# RGB_Station_v12.net
KiCad netlist of a schematic drawn in EAGLE
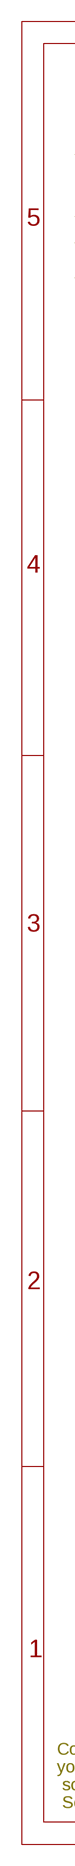
[diagram p0: schematic, sheet 1, part 1 of 2]
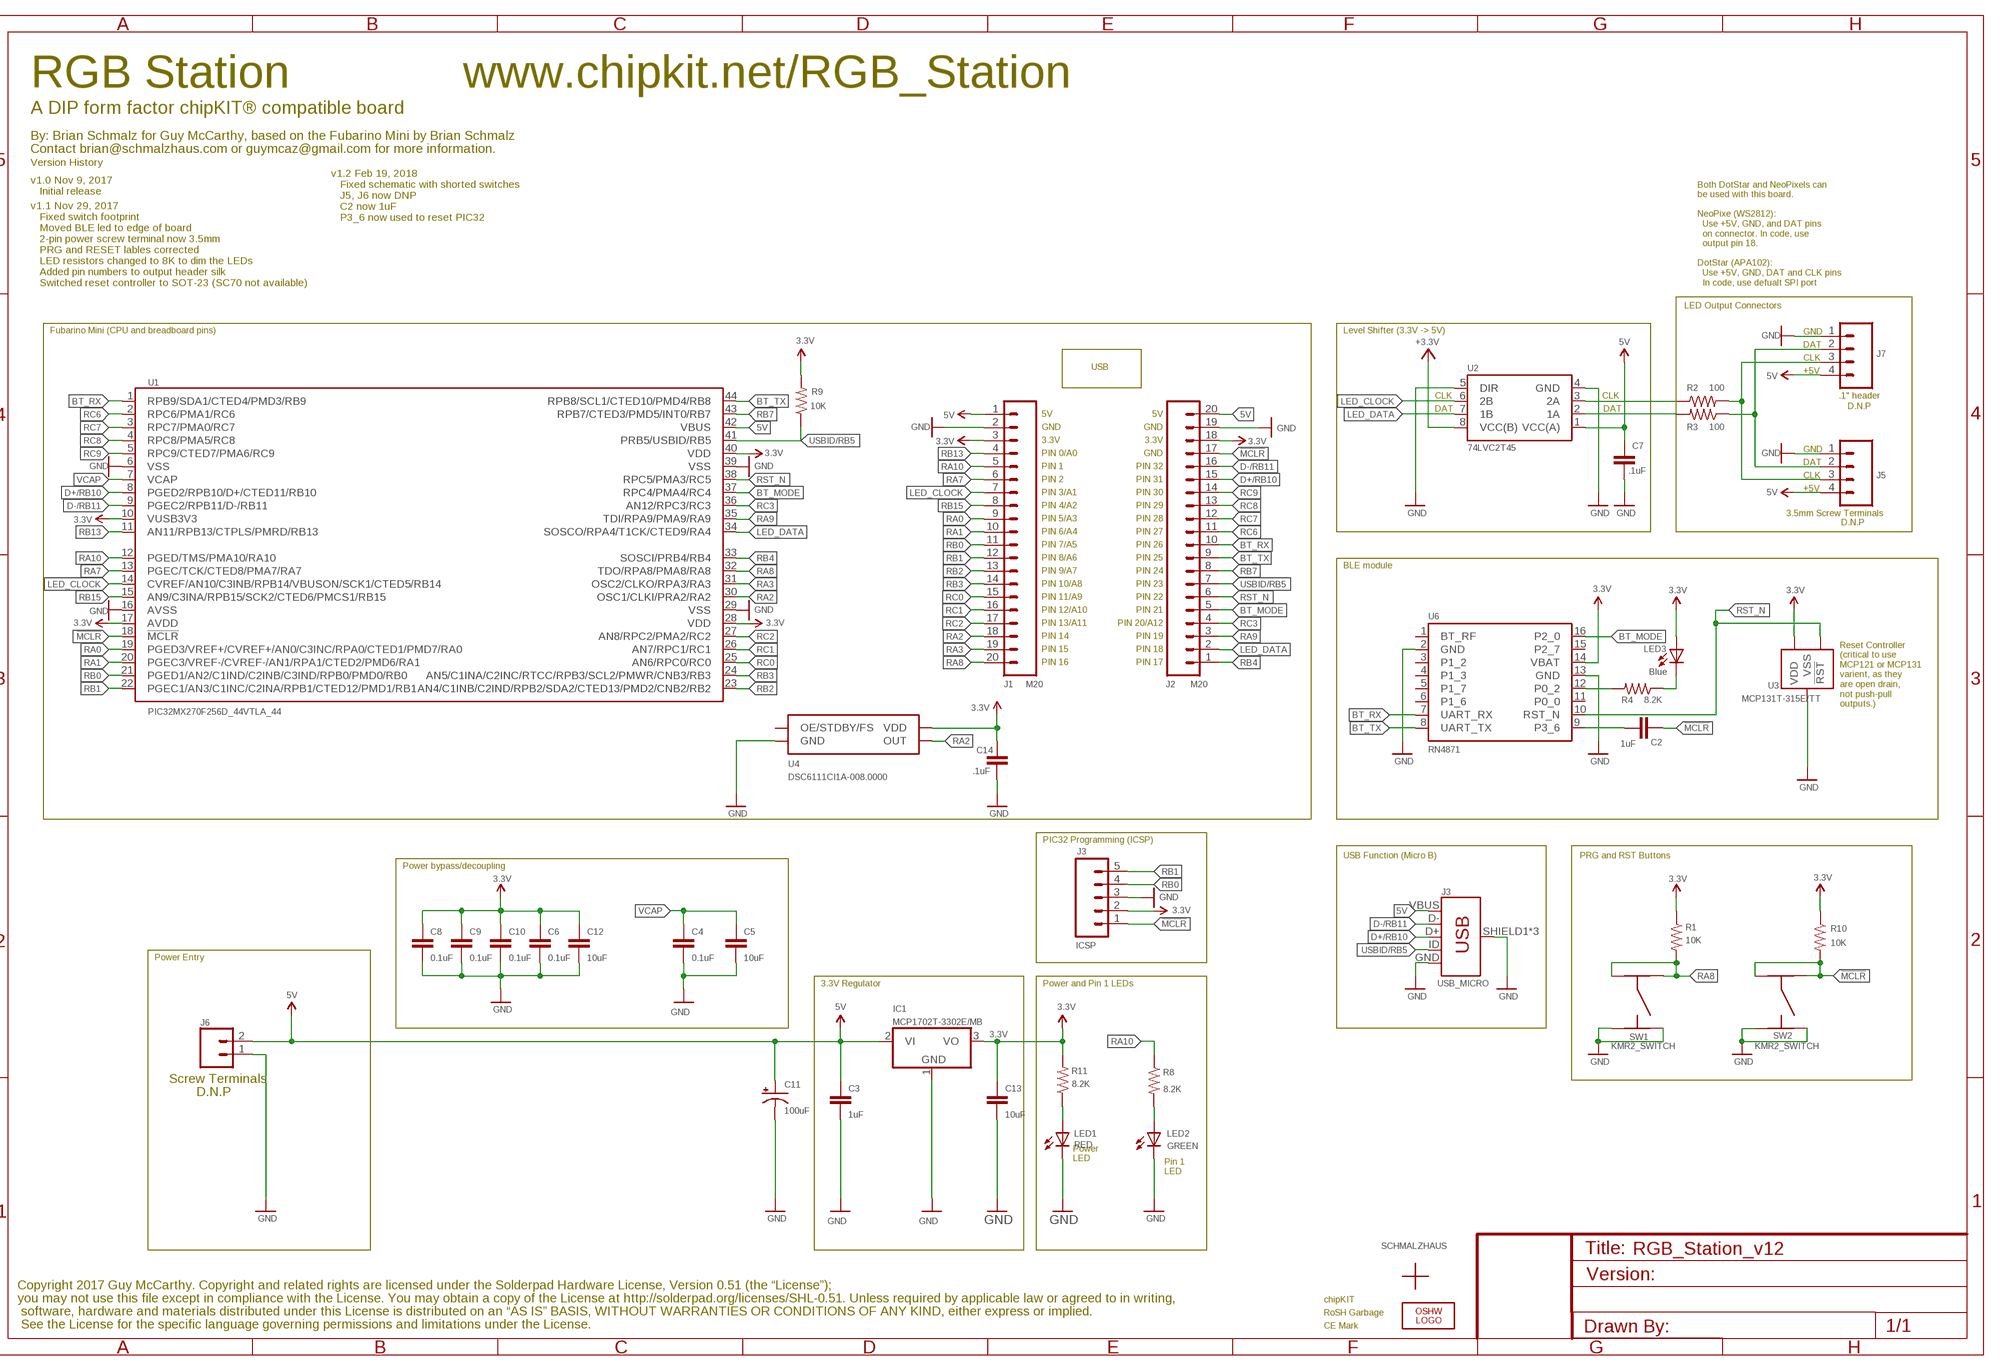
[diagram p1: schematic, sheet 1, part 2 of 2]

(export (version "E")
  (design (tool "Eeschema 10.0.6"))
  (components
    (comp (ref "C2")
      (value "1uF")
      (footprint "eagle-import:0603-CAP")
      (libsource (lib "eagle-import") (part "SparkFun-Capacitors_CAP0603-CAP"))
    )
    (comp (ref "C3")
      (value "1uF")
      (footprint "eagle-import:0603-CAP")
      (libsource (lib "eagle-import") (part "SparkFun_CAP0603-CAP"))
    )
    (comp (ref "C4")
      (value "0.1uF")
      (footprint "eagle-import:0603-CAP")
      (libsource (lib "eagle-import") (part "SparkFun_CAP0603-CAP"))
    )
    (comp (ref "C5")
      (value "10uF")
      (footprint "eagle-import:0805")
      (libsource (lib "eagle-import") (part "CAP0805"))
    )
    (comp (ref "C6")
      (value "0.1uF")
      (footprint "eagle-import:0603")
      (libsource (lib "eagle-import") (part "CAP0603"))
    )
    (comp (ref "C7")
      (value ".1uF")
      (footprint "eagle-import:0603-CAP")
      (libsource (lib "eagle-import") (part "SparkFun-Capacitors_CAP0603-CAP"))
    )
    (comp (ref "C8")
      (value "0.1uF")
      (footprint "eagle-import:0603-CAP")
      (libsource (lib "eagle-import") (part "SparkFun_CAP0603-CAP"))
    )
    (comp (ref "C9")
      (value "0.1uF")
      (footprint "eagle-import:0603-CAP")
      (libsource (lib "eagle-import") (part "SparkFun_CAP0603-CAP"))
    )
    (comp (ref "C10")
      (value "0.1uF")
      (footprint "eagle-import:0603")
      (libsource (lib "eagle-import") (part "CAP0603"))
    )
    (comp (ref "C11")
      (value "100uF")
      (footprint "eagle-import:PANASONIC_C")
      (libsource (lib "eagle-import") (part "CAP_POLC"))
    )
    (comp (ref "C12")
      (value "10uF")
      (footprint "eagle-import:0805")
      (libsource (lib "eagle-import") (part "CAP0805"))
    )
    (comp (ref "C13")
      (value "10uF")
      (footprint "eagle-import:0805")
      (libsource (lib "eagle-import") (part "SparkFun02-20-08_CAP0805"))
    )
    (comp (ref "C14")
      (value ".1uF")
      (footprint "eagle-import:0603-CAP")
      (libsource (lib "eagle-import") (part "SparkFun_CAP0603-CAP"))
    )
    (comp (ref "IC1")
      (value "MCP1702T-3302E/MB")
      (footprint "eagle-import:RGB_STATION_V12_LINEAR_SOT89")
      (libsource (lib "eagle-import") (part "RGB_STATION_V12_LINEAR_MCP1703MB28"))
    )
    (comp (ref "ICSP")
      (value "J3")
      (footprint "eagle-import:1X05_NOSILK")
      (libsource (lib "eagle-import") (part "M05NOSLILK"))
    )
    (comp (ref "J1")
      (value "M20")
      (footprint "eagle-import:1X20_NO_PIN1")
      (libsource (lib "eagle-import") (part "M20"))
    )
    (comp (ref "J2")
      (value "M20")
      (footprint "eagle-import:1X20_NO_PIN1")
      (libsource (lib "eagle-import") (part "M20"))
    )
    (comp (ref "J3")
      (value "USB_MICRO")
      (footprint "eagle-import:SPARKFUN-CONNECTORS_USB-B-MICRO-SMD")
      (libsource (lib "eagle-import") (part "SPARKFUN-CONNECTORS_USB_MICRO-B_FEMALE-SMT"))
    )
    (comp (ref "J5")
      (value "CONN_04SCREW")
      (footprint "eagle-import:SCREWTERMINAL-3.5MM-4@1")
      (libsource (lib "eagle-import") (part "CONN_04SCREW"))
    )
    (comp (ref "J6")
      (value "CONN_023.5MM")
      (footprint "eagle-import:SCREWTERMINAL-3.5MM-2")
      (libsource (lib "eagle-import") (part "CONN_023.5MM"))
    )
    (comp (ref "J7")
      (value "M04PTH")
      (footprint "eagle-import:1X04")
      (libsource (lib "eagle-import") (part "M04PTH"))
    )
    (comp (ref "LED1")
      (value "RED")
      (footprint "eagle-import:LED-0603")
      (libsource (lib "eagle-import") (part "LED0603"))
    )
    (comp (ref "LED2")
      (value "GREEN")
      (footprint "eagle-import:LED-0603")
      (libsource (lib "eagle-import") (part "LED0603"))
    )
    (comp (ref "LED3")
      (value "Blue")
      (footprint "eagle-import:LED-0603")
      (libsource (lib "eagle-import") (part "LED0603"))
    )
    (comp (ref "LOGO1")
      (value "OSHW_LOGO_8MILX0070-NT")
      (footprint "eagle-import:OSHW_8X70_NOTEXT")
      (libsource (lib "eagle-import") (part "OSHW_LOGO_8MILX0070-NT"))
    )
    (comp (ref "R1")
      (value "10K")
      (footprint "eagle-import:0603-RES")
      (libsource (lib "eagle-import") (part "RESISTOR0603-RES"))
    )
    (comp (ref "R2")
      (value "100")
      (footprint "eagle-import:0603-RES")
      (libsource (lib "eagle-import") (part "RESISTOR0603"))
    )
    (comp (ref "R3")
      (value "100")
      (footprint "eagle-import:0603-RES")
      (libsource (lib "eagle-import") (part "RESISTOR0603"))
    )
    (comp (ref "R4")
      (value "8.2K")
      (footprint "eagle-import:0603-RES")
      (libsource (lib "eagle-import") (part "RESISTOR0603-RES"))
    )
    (comp (ref "R8")
      (value "8.2K")
      (footprint "eagle-import:0603-RES")
      (libsource (lib "eagle-import") (part "RESISTOR0603-RES"))
    )
    (comp (ref "R9")
      (value "10K")
      (footprint "eagle-import:0603-RES")
      (libsource (lib "eagle-import") (part "RESISTOR0603-RES"))
    )
    (comp (ref "R10")
      (value "10K")
      (footprint "eagle-import:0603-RES")
      (libsource (lib "eagle-import") (part "RESISTOR0603-RES"))
    )
    (comp (ref "R11")
      (value "8.2K")
      (footprint "eagle-import:0603-RES")
      (libsource (lib "eagle-import") (part "RESISTOR0603-RES"))
    )
    (comp (ref "SW1")
      (value "KMR2_SWITCH")
      (footprint "eagle-import:KMR2_SWITCH")
      (libsource (lib "eagle-import") (part "KMR2_SWITCH"))
    )
    (comp (ref "SW2")
      (value "KMR2_SWITCH")
      (footprint "eagle-import:KMR2_SWITCH")
      (libsource (lib "eagle-import") (part "KMR2_SWITCH"))
    )
    (comp (ref "U$2")
      (value "CE_MARK5MM")
      (footprint "eagle-import:CE_5MM")
      (libsource (lib "eagle-import") (part "CE_MARK5MM"))
    )
    (comp (ref "U$3")
      (value "ROSH_GARBAGE")
      (footprint "eagle-import:ROHS_GARBAGE_5MM")
      (libsource (lib "eagle-import") (part "ROSH_GARBAGE"))
    )
    (comp (ref "U$4")
      (value "CHIPKIT2MM")
      (footprint "eagle-import:CHIPKIT_2MM")
      (libsource (lib "eagle-import") (part "CHIPKIT2MM"))
    )
    (comp (ref "U$5")
      (value "SCHMALZHAUSSCHMALZHAUS_SMALL")
      (footprint "eagle-import:SCHMALZHAUS_SMALL")
      (libsource (lib "eagle-import") (part "SCHMALZHAUSSCHMALZHAUS_SMALL"))
    )
    (comp (ref "U1")
      (value "PIC32MX270F256D_44VTLA_44")
      (footprint "eagle-import:QFN-44-8X8-NOPAD")
      (libsource (lib "eagle-import") (part "PIC32MX2XX_44QFN44"))
    )
    (comp (ref "U2")
      (value "74LVC2T45")
      (footprint "eagle-import:VSSOP8")
      (libsource (lib "eagle-import") (part "74LVC2T45"))
    )
    (comp (ref "U3")
      (value "MCP131T-315E/TT")
      (footprint "eagle-import:SOT23-3")
      (libsource (lib "eagle-import") (part "MCP1X2_RESET_CONTROLLER"))
    )
    (comp (ref "U4")
      (value "DSC6111CI1A-008.0000")
      (footprint "eagle-import:CDFN-4_3.2X2.5")
      (libsource (lib "eagle-import") (part "DSC61XX"))
    )
    (comp (ref "U6")
      (value "RN4871")
      (footprint "eagle-import:RN4871")
      (libsource (lib "eagle-import") (part "RN4871"))
    )
  )
  (nets
    (net (code "1") (name "+3.3V") (class "Default")
      (node (ref "C10") (pin "1") (pinfunction "1_1") (pintype "passive"))
      (node (ref "C12") (pin "1") (pinfunction "1_1") (pintype "passive"))
      (node (ref "C13") (pin "1") (pinfunction "1_1") (pintype "passive"))
      (node (ref "C14") (pin "2") (pinfunction "2_2") (pintype "passive"))
      (node (ref "C6") (pin "1") (pinfunction "1_1") (pintype "passive"))
      (node (ref "C8") (pin "1") (pinfunction "1_1") (pintype "passive"))
      (node (ref "C9") (pin "1") (pinfunction "1_1") (pintype "passive"))
      (node (ref "IC1") (pin "3") (pinfunction "VO_3") (pintype "passive"))
      (node (ref "ICSP") (pin "2") (pinfunction "2_2") (pintype "passive"))
      (node (ref "J1") (pin "3") (pinfunction "3_3") (pintype "passive"))
      (node (ref "J2") (pin "18") (pinfunction "18_18") (pintype "passive"))
      (node (ref "LED3") (pin "A") (pinfunction "A_A") (pintype "passive"))
      (node (ref "R1") (pin "1") (pinfunction "1_1") (pintype "passive"))
      (node (ref "R10") (pin "1") (pinfunction "1_1") (pintype "passive"))
      (node (ref "R11") (pin "2") (pinfunction "2_2") (pintype "passive"))
      (node (ref "R9") (pin "2") (pinfunction "2_2") (pintype "passive"))
      (node (ref "U1") (pin "10") (pinfunction "VUSB3V3_10") (pintype "bidirectional"))
      (node (ref "U1") (pin "17") (pinfunction "AVDD_17") (pintype "bidirectional"))
      (node (ref "U1") (pin "28") (pinfunction "VDD_28") (pintype "bidirectional"))
      (node (ref "U1") (pin "40") (pinfunction "VDD_40") (pintype "bidirectional"))
      (node (ref "U2") (pin "8") (pinfunction "VCC(B)_8") (pintype "bidirectional"))
      (node (ref "U3") (pin "2") (pinfunction "VDD_2") (pintype "bidirectional"))
      (node (ref "U4") (pin "P4") (pinfunction "VDD_P4") (pintype "bidirectional"))
      (node (ref "U6") (pin "14") (pinfunction "VBAT_14") (pintype "bidirectional"))
    )
    (net (code "2") (name "/~{MCLR}") (class "Default")
      (node (ref "C2") (pin "2") (pinfunction "2_2") (pintype "passive"))
      (node (ref "ICSP") (pin "1") (pinfunction "1_1") (pintype "passive"))
      (node (ref "J2") (pin "17") (pinfunction "17_17") (pintype "passive"))
      (node (ref "R10") (pin "2") (pinfunction "2_2") (pintype "passive"))
      (node (ref "SW2") (pin "P1") (pinfunction "P1_P1") (pintype "bidirectional"))
      (node (ref "SW2") (pin "P4") (pinfunction "P4_P4") (pintype "bidirectional"))
      (node (ref "U1") (pin "18") (pinfunction "~{MCLR}_18") (pintype "bidirectional"))
    )
    (net (code "3") (name "5V") (class "Default")
      (node (ref "C11") (pin "+") (pinfunction "+_+") (pintype "passive"))
      (node (ref "C3") (pin "1") (pinfunction "1_1") (pintype "passive"))
      (node (ref "C7") (pin "2") (pinfunction "2_2") (pintype "passive"))
      (node (ref "IC1") (pin "2") (pinfunction "VI_2") (pintype "input"))
      (node (ref "IC1") (pin "2@1") (pinfunction "VI1_2@1") (pintype "input"))
      (node (ref "J1") (pin "1") (pinfunction "1_1") (pintype "passive"))
      (node (ref "J2") (pin "20") (pinfunction "20_20") (pintype "passive"))
      (node (ref "J3") (pin "VBUS") (pinfunction "VBUS_VBUS") (pintype "power_in"))
      (node (ref "J5") (pin "4") (pinfunction "4_4") (pintype "passive"))
      (node (ref "J6") (pin "2") (pinfunction "2_2") (pintype "passive"))
      (node (ref "J7") (pin "4") (pinfunction "4_4") (pintype "passive"))
      (node (ref "U1") (pin "42") (pinfunction "VBUS_42") (pintype "bidirectional"))
      (node (ref "U2") (pin "1") (pinfunction "VCC(A)_1") (pintype "bidirectional"))
    )
    (net (code "4") (name "BT_MODE") (class "Default")
      (node (ref "J2") (pin "5") (pinfunction "5_5") (pintype "passive"))
      (node (ref "U1") (pin "37") (pinfunction "RPC4/PMA4/RC4_37") (pintype "bidirectional"))
      (node (ref "U6") (pin "16") (pinfunction "P2_0_16") (pintype "bidirectional"))
    )
    (net (code "5") (name "BT_RX") (class "Default")
      (node (ref "J2") (pin "10") (pinfunction "10_10") (pintype "passive"))
      (node (ref "U1") (pin "1") (pinfunction "RPB9/SDA1/CTED4/PMD3/RB9_1") (pintype "bidirectional"))
      (node (ref "U6") (pin "7") (pinfunction "UART_RX_7") (pintype "bidirectional"))
    )
    (net (code "6") (name "BT_TX") (class "Default")
      (node (ref "J2") (pin "9") (pinfunction "9_9") (pintype "passive"))
      (node (ref "U1") (pin "44") (pinfunction "RPB8/SCL1/CTED10/PMD4/RB8_44") (pintype "bidirectional"))
      (node (ref "U6") (pin "8") (pinfunction "UART_TX_8") (pintype "bidirectional"))
    )
    (net (code "7") (name "D+{slash}RB10") (class "Default")
      (node (ref "J2") (pin "15") (pinfunction "15_15") (pintype "passive"))
      (node (ref "J3") (pin "D+") (pinfunction "D+_D+") (pintype "bidirectional"))
      (node (ref "U1") (pin "8") (pinfunction "PGED2/RPB10/D+/CTED11/RB10_8") (pintype "bidirectional"))
    )
    (net (code "8") (name "D-{slash}RB11") (class "Default")
      (node (ref "J2") (pin "16") (pinfunction "16_16") (pintype "passive"))
      (node (ref "J3") (pin "D-") (pinfunction "D-_D-") (pintype "bidirectional"))
      (node (ref "U1") (pin "9") (pinfunction "PGEC2/RPB11/D-/RB11_9") (pintype "bidirectional"))
    )
    (net (code "9") (name "GND") (class "Default")
      (node (ref "C10") (pin "2") (pinfunction "2_2") (pintype "passive"))
      (node (ref "C11") (pin "-") (pinfunction "-_-") (pintype "passive"))
      (node (ref "C12") (pin "2") (pinfunction "2_2") (pintype "passive"))
      (node (ref "C13") (pin "2") (pinfunction "2_2") (pintype "passive"))
      (node (ref "C14") (pin "1") (pinfunction "1_1") (pintype "passive"))
      (node (ref "C3") (pin "2") (pinfunction "2_2") (pintype "passive"))
      (node (ref "C4") (pin "2") (pinfunction "2_2") (pintype "passive"))
      (node (ref "C5") (pin "2") (pinfunction "2_2") (pintype "passive"))
      (node (ref "C6") (pin "2") (pinfunction "2_2") (pintype "passive"))
      (node (ref "C7") (pin "1") (pinfunction "1_1") (pintype "passive"))
      (node (ref "C8") (pin "2") (pinfunction "2_2") (pintype "passive"))
      (node (ref "C9") (pin "2") (pinfunction "2_2") (pintype "passive"))
      (node (ref "IC1") (pin "1") (pinfunction "GND_1") (pintype "passive"))
      (node (ref "ICSP") (pin "3") (pinfunction "3_3") (pintype "passive"))
      (node (ref "J1") (pin "2") (pinfunction "2_2") (pintype "passive"))
      (node (ref "J2") (pin "19") (pinfunction "19_19") (pintype "passive"))
      (node (ref "J3") (pin "GND") (pinfunction "GND_GND") (pintype "power_in"))
      (node (ref "J3") (pin "SHIELD1") (pinfunction "SHIELD_SHIELD1") (pintype "bidirectional"))
      (node (ref "J3") (pin "SHIELD2") (pinfunction "SHIELD_SHIELD2") (pintype "bidirectional"))
      (node (ref "J3") (pin "SHIELD3") (pinfunction "SHIELD_SHIELD3") (pintype "bidirectional"))
      (node (ref "J5") (pin "1") (pinfunction "1_1") (pintype "passive"))
      (node (ref "J6") (pin "1") (pinfunction "1_1") (pintype "passive"))
      (node (ref "J7") (pin "1") (pinfunction "1_1") (pintype "passive"))
      (node (ref "LED1") (pin "C") (pinfunction "C_C") (pintype "passive"))
      (node (ref "LED2") (pin "C") (pinfunction "C_C") (pintype "passive"))
      (node (ref "SW1") (pin "P2") (pinfunction "P2_P2") (pintype "bidirectional"))
      (node (ref "SW1") (pin "P3") (pinfunction "P3_P3") (pintype "bidirectional"))
      (node (ref "SW2") (pin "P2") (pinfunction "P2_P2") (pintype "bidirectional"))
      (node (ref "SW2") (pin "P3") (pinfunction "P3_P3") (pintype "bidirectional"))
      (node (ref "U1") (pin "16") (pinfunction "AVSS_16") (pintype "bidirectional"))
      (node (ref "U1") (pin "29") (pinfunction "VSS_29") (pintype "bidirectional"))
      (node (ref "U1") (pin "39") (pinfunction "VSS_39") (pintype "bidirectional"))
      (node (ref "U1") (pin "6") (pinfunction "VSS_6") (pintype "bidirectional"))
      (node (ref "U2") (pin "4") (pinfunction "GND_4") (pintype "bidirectional"))
      (node (ref "U2") (pin "5") (pinfunction "DIR_5") (pintype "bidirectional"))
      (node (ref "U3") (pin "3") (pinfunction "VSS_3") (pintype "bidirectional"))
      (node (ref "U4") (pin "P2") (pinfunction "GND_P2") (pintype "bidirectional"))
      (node (ref "U6") (pin "13") (pinfunction "GND_13") (pintype "bidirectional"))
      (node (ref "U6") (pin "2") (pinfunction "GND_2") (pintype "bidirectional"))
    )
    (net (code "10") (name "LED_CLOCK") (class "Default")
      (node (ref "J1") (pin "7") (pinfunction "7_7") (pintype "passive"))
      (node (ref "U1") (pin "14") (pinfunction "CVREF/AN10/C3INB/RPB14/VBUSON/SCK1/CTED5/RB14_14") (pintype "bidirectional"))
      (node (ref "U2") (pin "6") (pinfunction "2B_6") (pintype "bidirectional"))
    )
    (net (code "11") (name "LED_DATA") (class "Default")
      (node (ref "J2") (pin "2") (pinfunction "2_2") (pintype "passive"))
      (node (ref "U1") (pin "34") (pinfunction "SOSCO/RPA4/T1CK/CTED9/RA4_34") (pintype "bidirectional"))
      (node (ref "U2") (pin "7") (pinfunction "1B_7") (pintype "bidirectional"))
    )
    (net (code "12") (name "Net-(J5-Pad2)") (class "Default")
      (node (ref "J5") (pin "2") (pinfunction "2_2") (pintype "passive"))
      (node (ref "J7") (pin "2") (pinfunction "2_2") (pintype "passive"))
      (node (ref "R3") (pin "1") (pinfunction "1_1") (pintype "passive"))
    )
    (net (code "13") (name "Net-(J5-Pad3)") (class "Default")
      (node (ref "J5") (pin "3") (pinfunction "3_3") (pintype "passive"))
      (node (ref "J7") (pin "3") (pinfunction "3_3") (pintype "passive"))
      (node (ref "R2") (pin "2") (pinfunction "2_2") (pintype "passive"))
    )
    (net (code "14") (name "Net-(LED1-PadA)") (class "Default")
      (node (ref "LED1") (pin "A") (pinfunction "A_A") (pintype "passive"))
      (node (ref "R11") (pin "1") (pinfunction "1_1") (pintype "passive"))
    )
    (net (code "15") (name "Net-(LED2-PadA)") (class "Default")
      (node (ref "LED2") (pin "A") (pinfunction "A_A") (pintype "passive"))
      (node (ref "R8") (pin "2") (pinfunction "2_2") (pintype "passive"))
    )
    (net (code "16") (name "Net-(LED3-PadC)") (class "Default")
      (node (ref "LED3") (pin "C") (pinfunction "C_C") (pintype "passive"))
      (node (ref "R4") (pin "1") (pinfunction "1_1") (pintype "passive"))
    )
    (net (code "17") (name "Net-(U2-1A)") (class "Default")
      (node (ref "R3") (pin "2") (pinfunction "2_2") (pintype "passive"))
      (node (ref "U2") (pin "2") (pinfunction "1A_2") (pintype "bidirectional"))
    )
    (net (code "18") (name "Net-(U2-2A)") (class "Default")
      (node (ref "R2") (pin "1") (pinfunction "1_1") (pintype "passive"))
      (node (ref "U2") (pin "3") (pinfunction "2A_3") (pintype "bidirectional"))
    )
    (net (code "19") (name "Net-(U6-P0_2)") (class "Default")
      (node (ref "R4") (pin "2") (pinfunction "2_2") (pintype "passive"))
      (node (ref "U6") (pin "12") (pinfunction "P0_2_12") (pintype "bidirectional"))
    )
    (net (code "20") (name "Net-(U6-P3_6)") (class "Default")
      (node (ref "C2") (pin "1") (pinfunction "1_1") (pintype "passive"))
      (node (ref "U6") (pin "9") (pinfunction "P3_6_9") (pintype "bidirectional"))
    )
    (net (code "21") (name "RA0") (class "Default")
      (node (ref "J1") (pin "9") (pinfunction "9_9") (pintype "passive"))
      (node (ref "U1") (pin "19") (pinfunction "PGED3/VREF+/CVREF+/AN0/C3INC/RPA0/CTED1/PMD7/RA0_19") (pintype "bidirectional"))
    )
    (net (code "22") (name "RA1") (class "Default")
      (node (ref "J1") (pin "10") (pinfunction "10_10") (pintype "passive"))
      (node (ref "U1") (pin "20") (pinfunction "PGEC3/VREF-/CVREF-/AN1/RPA1/CTED2/PMD6/RA1_20") (pintype "bidirectional"))
    )
    (net (code "23") (name "RA2") (class "Default")
      (node (ref "J1") (pin "18") (pinfunction "18_18") (pintype "passive"))
      (node (ref "U1") (pin "30") (pinfunction "OSC1/CLKI/PRA2/RA2_30") (pintype "bidirectional"))
      (node (ref "U4") (pin "P3") (pinfunction "OUT_P3") (pintype "bidirectional"))
    )
    (net (code "24") (name "RA3") (class "Default")
      (node (ref "J1") (pin "19") (pinfunction "19_19") (pintype "passive"))
      (node (ref "U1") (pin "31") (pinfunction "OSC2/CLKO/RPA3/RA3_31") (pintype "bidirectional"))
    )
    (net (code "25") (name "RA7") (class "Default")
      (node (ref "J1") (pin "6") (pinfunction "6_6") (pintype "passive"))
      (node (ref "U1") (pin "13") (pinfunction "PGEC/TCK/CTED8/PMA7/RA7_13") (pintype "bidirectional"))
    )
    (net (code "26") (name "RA8") (class "Default")
      (node (ref "J1") (pin "20") (pinfunction "20_20") (pintype "passive"))
      (node (ref "R1") (pin "2") (pinfunction "2_2") (pintype "passive"))
      (node (ref "SW1") (pin "P1") (pinfunction "P1_P1") (pintype "bidirectional"))
      (node (ref "SW1") (pin "P4") (pinfunction "P4_P4") (pintype "bidirectional"))
      (node (ref "U1") (pin "32") (pinfunction "TDO/RPA8/PMA8/RA8_32") (pintype "bidirectional"))
    )
    (net (code "27") (name "RA9") (class "Default")
      (node (ref "J2") (pin "3") (pinfunction "3_3") (pintype "passive"))
      (node (ref "U1") (pin "35") (pinfunction "TDI/RPA9/PMA9/RA9_35") (pintype "bidirectional"))
    )
    (net (code "28") (name "RA10") (class "Default")
      (node (ref "J1") (pin "5") (pinfunction "5_5") (pintype "passive"))
      (node (ref "R8") (pin "1") (pinfunction "1_1") (pintype "passive"))
      (node (ref "U1") (pin "12") (pinfunction "PGED/TMS/PMA10/RA10_12") (pintype "bidirectional"))
    )
    (net (code "29") (name "RB0") (class "Default")
      (node (ref "ICSP") (pin "4") (pinfunction "4_4") (pintype "passive"))
      (node (ref "J1") (pin "11") (pinfunction "11_11") (pintype "passive"))
      (node (ref "U1") (pin "21") (pinfunction "PGED1/AN2/C1IND/C2INB/C3IND/RPB0/PMD0/RB0_21") (pintype "bidirectional"))
    )
    (net (code "30") (name "RB1") (class "Default")
      (node (ref "ICSP") (pin "5") (pinfunction "5_5") (pintype "passive"))
      (node (ref "J1") (pin "12") (pinfunction "12_12") (pintype "passive"))
      (node (ref "U1") (pin "22") (pinfunction "PGEC1/AN3/C1INC/C2INA/RPB1/CTED12/PMD1/RB1_22") (pintype "bidirectional"))
    )
    (net (code "31") (name "RB2") (class "Default")
      (node (ref "J1") (pin "13") (pinfunction "13_13") (pintype "passive"))
      (node (ref "U1") (pin "23") (pinfunction "AN4/C1INB/C2IND/RPB2/SDA2/CTED13/PMD2/CNB2/RB2_23") (pintype "bidirectional"))
    )
    (net (code "32") (name "RB3") (class "Default")
      (node (ref "J1") (pin "14") (pinfunction "14_14") (pintype "passive"))
      (node (ref "U1") (pin "24") (pinfunction "AN5/C1INA/C2INC/RTCC/RPB3/SCL2/PMWR/CNB3/RB3_24") (pintype "bidirectional"))
    )
    (net (code "33") (name "RB4") (class "Default")
      (node (ref "J2") (pin "1") (pinfunction "1_1") (pintype "passive"))
      (node (ref "U1") (pin "33") (pinfunction "SOSCI/PRB4/RB4_33") (pintype "bidirectional"))
    )
    (net (code "34") (name "RB7") (class "Default")
      (node (ref "J2") (pin "8") (pinfunction "8_8") (pintype "passive"))
      (node (ref "U1") (pin "43") (pinfunction "RPB7/CTED3/PMD5/INT0/RB7_43") (pintype "bidirectional"))
    )
    (net (code "35") (name "RB13") (class "Default")
      (node (ref "J1") (pin "4") (pinfunction "4_4") (pintype "passive"))
      (node (ref "U1") (pin "11") (pinfunction "AN11/RPB13/CTPLS/PMRD/RB13_11") (pintype "bidirectional"))
    )
    (net (code "36") (name "RB15") (class "Default")
      (node (ref "J1") (pin "8") (pinfunction "8_8") (pintype "passive"))
      (node (ref "U1") (pin "15") (pinfunction "AN9/C3INA/RPB15/SCK2/CTED6/PMCS1/RB15_15") (pintype "bidirectional"))
    )
    (net (code "37") (name "RC0") (class "Default")
      (node (ref "J1") (pin "15") (pinfunction "15_15") (pintype "passive"))
      (node (ref "U1") (pin "25") (pinfunction "AN6/RPC0/RC0_25") (pintype "bidirectional"))
    )
    (net (code "38") (name "RC1") (class "Default")
      (node (ref "J1") (pin "16") (pinfunction "16_16") (pintype "passive"))
      (node (ref "U1") (pin "26") (pinfunction "AN7/RPC1/RC1_26") (pintype "bidirectional"))
    )
    (net (code "39") (name "RC2") (class "Default")
      (node (ref "J1") (pin "17") (pinfunction "17_17") (pintype "passive"))
      (node (ref "U1") (pin "27") (pinfunction "AN8/RPC2/PMA2/RC2_27") (pintype "bidirectional"))
    )
    (net (code "40") (name "RC3") (class "Default")
      (node (ref "J2") (pin "4") (pinfunction "4_4") (pintype "passive"))
      (node (ref "U1") (pin "36") (pinfunction "AN12/RPC3/RC3_36") (pintype "bidirectional"))
    )
    (net (code "41") (name "RC6") (class "Default")
      (node (ref "J2") (pin "11") (pinfunction "11_11") (pintype "passive"))
      (node (ref "U1") (pin "2") (pinfunction "RPC6/PMA1/RC6_2") (pintype "bidirectional"))
    )
    (net (code "42") (name "RC7") (class "Default")
      (node (ref "J2") (pin "12") (pinfunction "12_12") (pintype "passive"))
      (node (ref "U1") (pin "3") (pinfunction "RPC7/PMA0/RC7_3") (pintype "bidirectional"))
    )
    (net (code "43") (name "RC8") (class "Default")
      (node (ref "J2") (pin "13") (pinfunction "13_13") (pintype "passive"))
      (node (ref "U1") (pin "4") (pinfunction "RPC8/PMA5/RC8_4") (pintype "bidirectional"))
    )
    (net (code "44") (name "RC9") (class "Default")
      (node (ref "J2") (pin "14") (pinfunction "14_14") (pintype "passive"))
      (node (ref "U1") (pin "5") (pinfunction "RPC9/CTED7/PMA6/RC9_5") (pintype "bidirectional"))
    )
    (net (code "45") (name "RST_N") (class "Default")
      (node (ref "J2") (pin "6") (pinfunction "6_6") (pintype "passive"))
      (node (ref "U1") (pin "38") (pinfunction "RPC5/PMA3/RC5_38") (pintype "bidirectional"))
      (node (ref "U3") (pin "1") (pinfunction "~{RST}_1") (pintype "bidirectional"))
      (node (ref "U6") (pin "10") (pinfunction "RST_N_10") (pintype "bidirectional"))
    )
    (net (code "46") (name "USBID{slash}RB5") (class "Default")
      (node (ref "J2") (pin "7") (pinfunction "7_7") (pintype "passive"))
      (node (ref "J3") (pin "ID") (pinfunction "ID_ID") (pintype "bidirectional"))
      (node (ref "R9") (pin "1") (pinfunction "1_1") (pintype "passive"))
      (node (ref "U1") (pin "41") (pinfunction "PRB5/USBID/RB5_41") (pintype "bidirectional"))
    )
    (net (code "47") (name "VCAP") (class "Default")
      (node (ref "C4") (pin "1") (pinfunction "1_1") (pintype "passive"))
      (node (ref "C5") (pin "1") (pinfunction "1_1") (pintype "passive"))
      (node (ref "U1") (pin "7") (pinfunction "VCAP_7") (pintype "bidirectional"))
    )
    (net (code "48") (name "unconnected-(U4-OE{slash}STDBY{slash}FS-PadP1)") (class "Default")
      (node (ref "U4") (pin "P1") (pinfunction "OE/STDBY/FS_P1") (pintype "bidirectional"))
    )
    (net (code "49") (name "unconnected-(U6-BT_RF-Pad1)") (class "Default")
      (node (ref "U6") (pin "1") (pinfunction "BT_RF_1") (pintype "bidirectional"))
    )
    (net (code "50") (name "unconnected-(U6-P0_0-Pad11)") (class "Default")
      (node (ref "U6") (pin "11") (pinfunction "P0_0_11") (pintype "bidirectional"))
    )
    (net (code "51") (name "unconnected-(U6-P1_2-Pad3)") (class "Default")
      (node (ref "U6") (pin "3") (pinfunction "P1_2_3") (pintype "bidirectional"))
    )
    (net (code "52") (name "unconnected-(U6-P1_3-Pad4)") (class "Default")
      (node (ref "U6") (pin "4") (pinfunction "P1_3_4") (pintype "bidirectional"))
    )
    (net (code "53") (name "unconnected-(U6-P1_6-Pad6)") (class "Default")
      (node (ref "U6") (pin "6") (pinfunction "P1_6_6") (pintype "bidirectional"))
    )
    (net (code "54") (name "unconnected-(U6-P1_7-Pad5)") (class "Default")
      (node (ref "U6") (pin "5") (pinfunction "P1_7_5") (pintype "bidirectional"))
    )
    (net (code "55") (name "unconnected-(U6-P2_7-Pad15)") (class "Default")
      (node (ref "U6") (pin "15") (pinfunction "P2_7_15") (pintype "bidirectional"))
    )
  )
)
